# INA219_sensor.net
KiCad netlist of a schematic drawn in Altium Designer
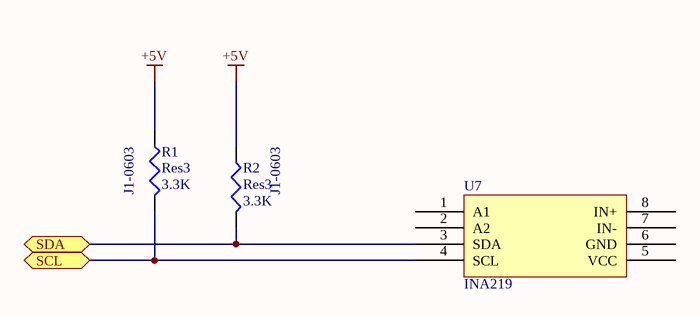
[diagram p0: INA219 sensor.SchDoc]

(export (version "E")
  (design (tool "Eeschema 10.0.6"))
  (components
    (comp (ref "R1")
      (value "Res3")
      (footprint "J1-0603")
      (description "Resistor")
      (fields
        (field (name "PACKAGEREFERENCE") "J1-0603")
        (field (name "ALTIUM_VALUE") "3.3K")
        (field (name "PUBLISHER") "Altium Limited")
      )
      (libsource (lib "Miscellaneous Devices") (part "Res3"))
    )
    (comp (ref "R2")
      (value "Res3")
      (footprint "J1-0603")
      (description "Resistor")
      (fields
        (field (name "PACKAGEREFERENCE") "J1-0603")
        (field (name "ALTIUM_VALUE") "3.3K")
        (field (name "PUBLISHER") "Altium Limited")
      )
      (libsource (lib "Miscellaneous Devices") (part "Res3"))
    )
    (comp (ref "U7") (value "INA219") (footprint "INA219") (libsource (lib "ATMEGA126") (part "INA219")))
  )
  (nets
    (net (code "1") (name "+5V") (class "Default")
      (node (ref "R1") (pin "1") (pinfunction "1_1") (pintype "passive"))
      (node (ref "R2") (pin "1") (pinfunction "1_1") (pintype "passive"))
    )
    (net (code "2") (name "/SCL") (class "Default")
      (node (ref "R1") (pin "2") (pinfunction "2_2") (pintype "passive"))
      (node (ref "U7") (pin "4") (pinfunction "SCL_4") (pintype "passive"))
    )
    (net (code "3") (name "/SDA") (class "Default")
      (node (ref "R2") (pin "2") (pinfunction "2_2") (pintype "passive"))
      (node (ref "U7") (pin "3") (pinfunction "SDA_3") (pintype "passive"))
    )
    (net (code "4") (name "unconnected-(U7-A1-Pad1)") (class "Default")
      (node (ref "U7") (pin "1") (pinfunction "A1_1") (pintype "passive"))
    )
    (net (code "5") (name "unconnected-(U7-A2-Pad2)") (class "Default")
      (node (ref "U7") (pin "2") (pinfunction "A2_2") (pintype "passive"))
    )
    (net (code "6") (name "unconnected-(U7-GND-Pad6)") (class "Default")
      (node (ref "U7") (pin "6") (pinfunction "GND_6") (pintype "passive"))
    )
    (net (code "7") (name "unconnected-(U7-IN+-Pad8)") (class "Default")
      (node (ref "U7") (pin "8") (pinfunction "IN+_8") (pintype "passive"))
    )
    (net (code "8") (name "unconnected-(U7-IN--Pad7)") (class "Default")
      (node (ref "U7") (pin "7") (pinfunction "IN-_7") (pintype "passive"))
    )
    (net (code "9") (name "unconnected-(U7-VCC-Pad5)") (class "Default")
      (node (ref "U7") (pin "5") (pinfunction "VCC_5") (pintype "passive"))
    )
  )
)
